# Peripherals.net
KiCad netlist of a schematic drawn in Altium Designer
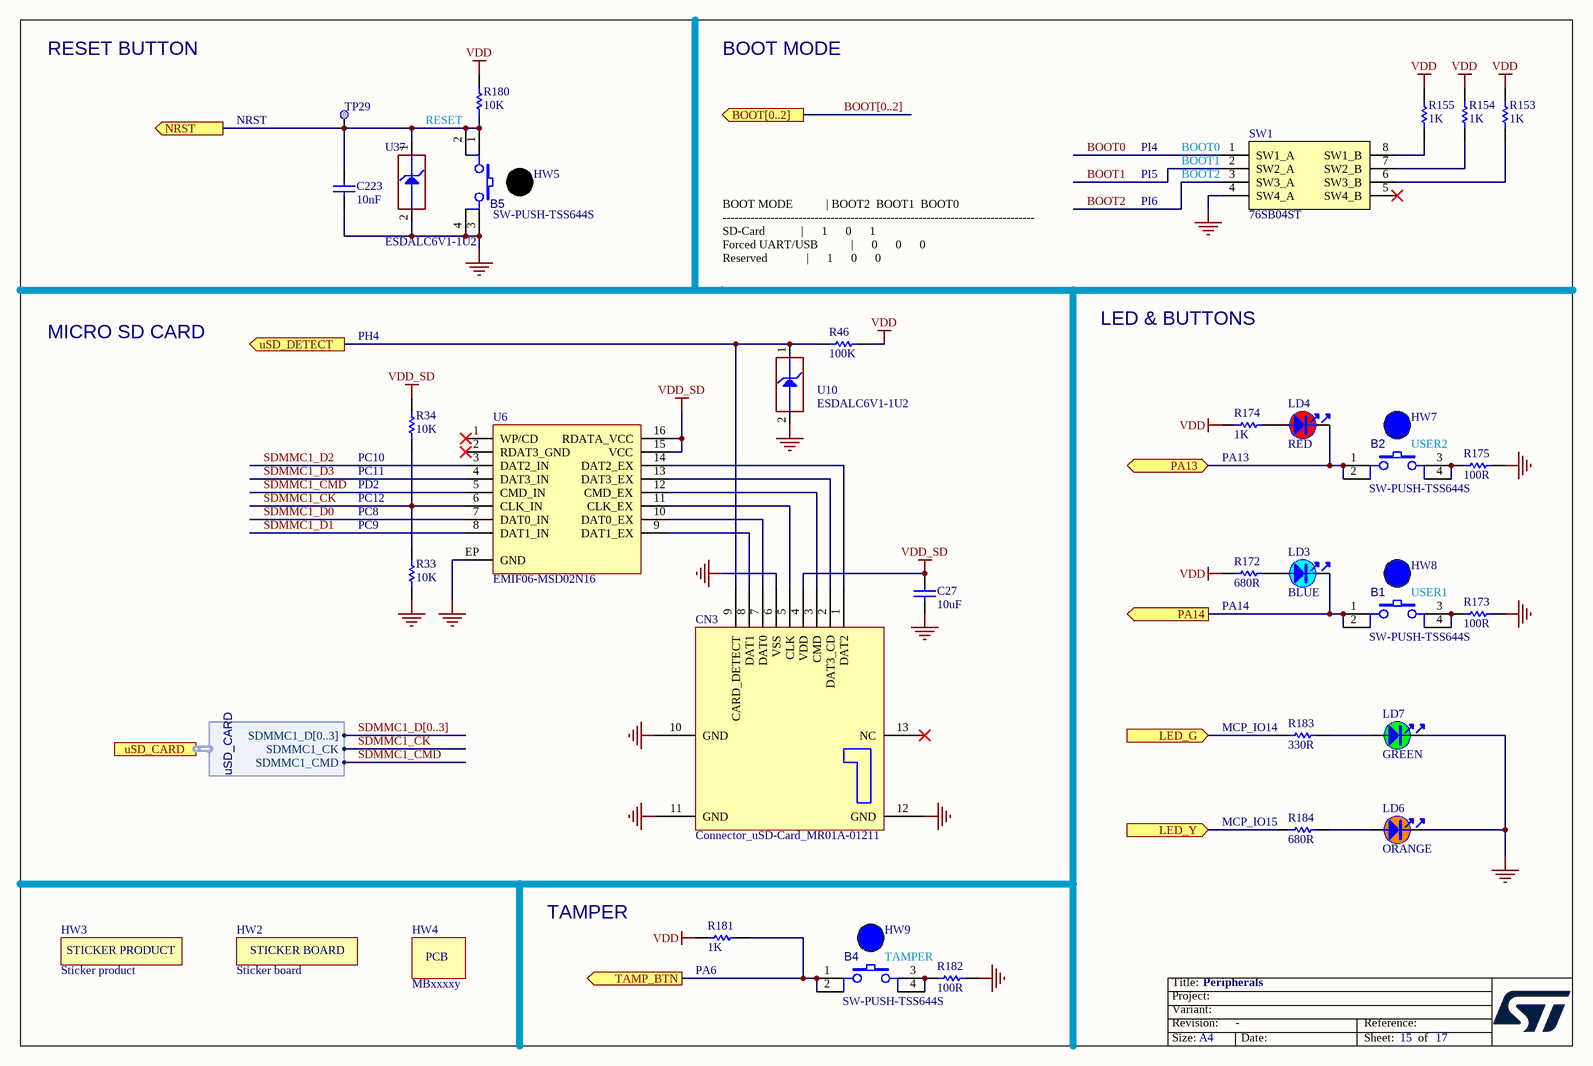
[diagram p0: Peripherals.SchDoc]

(export (version "E")
  (design (tool "Eeschema 10.0.6"))
  (components
    (comp (ref "B1")
      (value "SW-PUSH-TSS644S")
      (footprint "SWI_KNITTER_TSS644S")
      (description "Push Button, NO, 0.05A, 12V, 2.6N, SMD, 9.0x6.2mm, T=7.3mm, changeable caps KTSC-6xx")
      (fields
        (field (name "INTERNAL_PART_NUMBER") "MCD-02417")
        (field (name "MANUFACTURER_PART_NUMBER") "TSS644S")
      )
      (libsource (lib "MCD_PARTS_database") (part "SW_PUSH_SMD"))
    )
    (comp (ref "B2")
      (value "SW-PUSH-TSS644S")
      (footprint "SWI_KNITTER_TSS644S")
      (description "Push Button, NO, 0.05A, 12V, 2.6N, SMD, 9.0x6.2mm, T=7.3mm, changeable caps KTSC-6xx")
      (fields
        (field (name "INTERNAL_PART_NUMBER") "MCD-02417")
        (field (name "MANUFACTURER_PART_NUMBER") "TSS644S")
      )
      (libsource (lib "MCD_PARTS_database") (part "SW_PUSH_SMD"))
    )
    (comp (ref "B4")
      (value "SW-PUSH-TSS644S")
      (footprint "SWI_KNITTER_TSS644S")
      (description "Push Button, NO, 0.05A, 12V, 2.6N, SMD, 9.0x6.2mm, T=7.3mm, changeable caps KTSC-6xx")
      (fields
        (field (name "INTERNAL_PART_NUMBER") "MCD-02417")
        (field (name "MANUFACTURER_PART_NUMBER") "TSS644S")
      )
      (libsource (lib "MCD_PARTS_database") (part "SW_PUSH_SMD"))
    )
    (comp (ref "B5")
      (value "SW-PUSH-TSS644S")
      (footprint "SWI_KNITTER_TSS644S")
      (description "Push Button, NO, 0.05A, 12V, 2.6N, SMD, 9.0x6.2mm, T=7.3mm, changeable caps KTSC-6xx")
      (fields
        (field (name "INTERNAL_PART_NUMBER") "MCD-02417")
        (field (name "MANUFACTURER_PART_NUMBER") "TSS644S")
      )
      (libsource (lib "MCD_PARTS_database") (part "SW_PUSH_SMD"))
    )
    (comp (ref "C27")
      (value "10uF")
      (footprint "C0603")
      (description "Capacitor, MLCC, 10uF, 10V, X5R, +/-10%, 0603, T=0.8mm")
      (fields
        (field (name "INTERNAL_PART_NUMBER") "MCD-00099")
        (field (name "MANUFACTURER_PART_NUMBER") "GRM188R61A106KE69D")
      )
      (libsource (lib "MCD_PARTS_database") (part "Capacitor"))
    )
    (comp (ref "C223")
      (value "10nF")
      (footprint "C0402")
      (description "Capacitor, MLCC, 10nF, 50V, X7R, +/-10%, 0402, T=0.5mm")
      (fields
        (field (name "INTERNAL_PART_NUMBER") "MCD-02198")
        (field (name "MANUFACTURER_PART_NUMBER") "CC0402KRX7R9BB103")
      )
      (libsource (lib "MCD_PARTS_database") (part "Capacitor"))
    )
    (comp (ref "CN3")
      (value "Connector_uSD-Card_MR01A-01211")
      (footprint "CON_MICROSD_ATOM_MR01A-01211")
      (description "Connector_uSD Card, Top Mnt Push-Push")
      (fields
        (field (name "INTERNAL_PART_NUMBER") "MCD-00653")
        (field (name "MANUFACTURER_PART_NUMBER") "MR01A-01211")
      )
      (libsource (lib "MCD_PARTS_database") (part "MR01A-01211"))
    )
    (comp (ref "HW2")
      (value "Sticker board")
      (footprint "STICKER_BOARD_25X9")
      (description "Sticker Board 25x9 mm")
      (fields (field (name "INTERNAL_PART_NUMBER") "MCD-00235") (field (name "Comment") "STICKER_BOARD"))
      (libsource (lib "MCD_PARTS_database") (part "STICKER_BOARD"))
    )
    (comp (ref "HW3")
      (value "Sticker product")
      (footprint "STICKER_PRODUCT_25X9")
      (description "Sticker product 25x9 mm")
      (fields (field (name "INTERNAL_PART_NUMBER") "MCD-00547") (field (name "Comment") "STICKER_PRODUCT"))
      (libsource (lib "MCD_PARTS_database") (part "STICKER_PRODUCT"))
    )
    (comp (ref "HW4")
      (value "MBxxxxy")
      (description "PCB, xxxx for PCB number, Y for PCB revision")
      (fields
        (field (name "INTERNAL_PART_NUMBER") "MCD-00216")
        (field (name "MANUFACTURER_PART_NUMBER") "n/a")
      )
      (libsource (lib "MCD_PARTS_database") (part "PCB"))
    )
    (comp (ref "HW5")
      (value "SW-CAP-KTSC-62K")
      (description "Black round cap for TSS6x series")
      (fields
        (field (name "INTERNAL_PART_NUMBER") "MCD-02420")
        (field (name "MANUFACTURER") "KNITTER-SWITCH")
      )
      (libsource (lib "MCD_PARTS_database") (part "SW-CAP-Black"))
    )
    (comp (ref "HW7")
      (value "Blue Hat")
      (description "Switch hat, blue, For KTSC-62B")
      (fields (field (name "INTERNAL_PART_NUMBER") "MCD-02136") (field (name "MANUFACTURER") "APEM INC"))
      (libsource (lib "MCD_PARTS_database") (part "BUTTON_HAT_BLUE"))
    )
    (comp (ref "HW8")
      (value "Blue Hat")
      (description "Switch hat, blue, For KTSC-62B")
      (fields (field (name "INTERNAL_PART_NUMBER") "MCD-02136") (field (name "MANUFACTURER") "APEM INC"))
      (libsource (lib "MCD_PARTS_database") (part "BUTTON_HAT_BLUE"))
    )
    (comp (ref "HW9")
      (value "Blue Hat")
      (description "Switch hat, blue, For KTSC-62B")
      (fields (field (name "INTERNAL_PART_NUMBER") "MCD-02136") (field (name "MANUFACTURER") "APEM INC"))
      (libsource (lib "MCD_PARTS_database") (part "BUTTON_HAT_BLUE"))
    )
    (comp (ref "LD3")
      (value "BLUE")
      (footprint "LED_0603_SMD-B_BLUE_H0P4")
      (description "LED Blue, 0603 SMD, Forward Voltage Min=2,8V, Max=3,1V")
      (fields
        (field (name "INTERNAL_PART_NUMBER") "MCD-01131")
        (field (name "MANUFACTURER_PART_NUMBER") "19-217-BHC-ZL1M2RY-3T")
      )
      (libsource (lib "MCD_PARTS_database") (part "LED_blue"))
    )
    (comp (ref "LD4")
      (value "RED")
      (footprint "LED_0603_RED")
      (description "LED, Red, 0603")
      (fields
        (field (name "INTERNAL_PART_NUMBER") "MCD-00049")
        (field (name "MANUFACTURER_PART_NUMBER") "19-213-R6C-AP1Q2B/3T")
      )
      (libsource (lib "MCD_PARTS_database") (part "LED_red"))
    )
    (comp (ref "LD6")
      (value "ORANGE")
      (footprint "LED_0603_ORANGE_H0P4")
      (description "LED, Orange, 0603")
      (fields
        (field (name "INTERNAL_PART_NUMBER") "MCD-00321")
        (field (name "MANUFACTURER_PART_NUMBER") "19-217/S2C-AM2N2VY/3T")
      )
      (libsource (lib "MCD_PARTS_database") (part "LED_orange"))
    )
    (comp (ref "LD7")
      (value "GREEN")
      (footprint "LED_0603_GREEN")
      (description "LED, Green, 0603")
      (fields
        (field (name "INTERNAL_PART_NUMBER") "MCD-00050")
        (field (name "MANUFACTURER_PART_NUMBER") "19-213SYGC/S530-E2/TR8")
      )
      (libsource (lib "MCD_PARTS_database") (part "LED_green"))
    )
    (comp (ref "R33")
      (value "10K")
      (footprint "R0402")
      (description "Resistor, 10K, 0402, +/-1%, 1/16W")
      (fields
        (field (name "INTERNAL_PART_NUMBER") "MCD-00053")
        (field (name "MANUFACTURER_PART_NUMBER") "RC0402FR-0710KL")
      )
      (libsource (lib "MCD_PARTS_database") (part "Resistor"))
    )
    (comp (ref "R34")
      (value "10K")
      (footprint "R0402")
      (description "Resistor, 10K, 0402, +/-1%, 1/16W")
      (fields
        (field (name "INTERNAL_PART_NUMBER") "MCD-00053")
        (field (name "MANUFACTURER_PART_NUMBER") "RC0402FR-0710KL")
      )
      (libsource (lib "MCD_PARTS_database") (part "Resistor"))
    )
    (comp (ref "R46")
      (value "100K")
      (footprint "R0402")
      (description "Resistor, 100K, 0402, +/-1%, 1/16W")
      (fields (field (name "INTERNAL_PART_NUMBER") "MCD-00059") (field (name "MANUFACTURER") "YAGEO"))
      (libsource (lib "MCD_PARTS_database") (part "Resistor"))
    )
    (comp (ref "R153")
      (value "1K")
      (footprint "R0402")
      (description "Resistor, 1K, 0402, +/-1%,1/16W")
      (fields
        (field (name "INTERNAL_PART_NUMBER") "MCD-00061")
        (field (name "MANUFACTURER_PART_NUMBER") "RC0402FR-071KL")
      )
      (libsource (lib "MCD_PARTS_database") (part "Resistor"))
    )
    (comp (ref "R154")
      (value "1K")
      (footprint "R0402")
      (description "Resistor, 1K, 0402, +/-1%,1/16W")
      (fields
        (field (name "INTERNAL_PART_NUMBER") "MCD-00061")
        (field (name "MANUFACTURER_PART_NUMBER") "RC0402FR-071KL")
      )
      (libsource (lib "MCD_PARTS_database") (part "Resistor"))
    )
    (comp (ref "R155")
      (value "1K")
      (footprint "R0402")
      (description "Resistor, 1K, 0402, +/-1%,1/16W")
      (fields
        (field (name "INTERNAL_PART_NUMBER") "MCD-00061")
        (field (name "MANUFACTURER_PART_NUMBER") "RC0402FR-071KL")
      )
      (libsource (lib "MCD_PARTS_database") (part "Resistor"))
    )
    (comp (ref "R172")
      (value "680R")
      (footprint "R0402")
      (description "Resistor, 680R, 0402, +/-1%, 1/16W")
      (fields
        (field (name "INTERNAL_PART_NUMBER") "MCD-00507")
        (field (name "MANUFACTURER_PART_NUMBER") "RC0402FR-07680RL")
      )
      (libsource (lib "MCD_PARTS_database") (part "Resistor"))
    )
    (comp (ref "R173")
      (value "100R")
      (footprint "R0402")
      (description "Resistor, 100R, 0402, +/- 1%, 1/16W")
      (fields
        (field (name "INTERNAL_PART_NUMBER") "MCD-00067")
        (field (name "MANUFACTURER_PART_NUMBER") "RC0402FR-07100RL")
      )
      (libsource (lib "MCD_PARTS_database") (part "Resistor"))
    )
    (comp (ref "R174")
      (value "1K")
      (footprint "R0402")
      (description "Resistor, 1K, 0402, +/-1%,1/16W")
      (fields
        (field (name "INTERNAL_PART_NUMBER") "MCD-00061")
        (field (name "MANUFACTURER_PART_NUMBER") "RC0402FR-071KL")
      )
      (libsource (lib "MCD_PARTS_database") (part "Resistor"))
    )
    (comp (ref "R175")
      (value "100R")
      (footprint "R0402")
      (description "Resistor, 100R, 0402, +/- 1%, 1/16W")
      (fields
        (field (name "INTERNAL_PART_NUMBER") "MCD-00067")
        (field (name "MANUFACTURER_PART_NUMBER") "RC0402FR-07100RL")
      )
      (libsource (lib "MCD_PARTS_database") (part "Resistor"))
    )
    (comp (ref "R180")
      (value "10K")
      (footprint "R0402")
      (description "Resistor, 10K, 0402, +/-1%, 1/16W")
      (fields
        (field (name "INTERNAL_PART_NUMBER") "MCD-00053")
        (field (name "MANUFACTURER_PART_NUMBER") "RC0402FR-0710KL")
      )
      (libsource (lib "MCD_PARTS_database") (part "Resistor"))
    )
    (comp (ref "R181")
      (value "1K")
      (footprint "R0402")
      (description "Resistor, 1K, 0402, +/-1%,1/16W")
      (fields
        (field (name "INTERNAL_PART_NUMBER") "MCD-00061")
        (field (name "MANUFACTURER_PART_NUMBER") "RC0402FR-071KL")
      )
      (libsource (lib "MCD_PARTS_database") (part "Resistor"))
    )
    (comp (ref "R182")
      (value "100R")
      (footprint "R0402")
      (description "Resistor, 100R, 0402, +/- 1%, 1/16W")
      (fields
        (field (name "INTERNAL_PART_NUMBER") "MCD-00067")
        (field (name "MANUFACTURER_PART_NUMBER") "RC0402FR-07100RL")
      )
      (libsource (lib "MCD_PARTS_database") (part "Resistor"))
    )
    (comp (ref "R183")
      (value "330R")
      (footprint "R0402")
      (description "Resistor, 330R, 0402, +/-1%, 1/16W")
      (fields
        (field (name "INTERNAL_PART_NUMBER") "MCD-00062")
        (field (name "MANUFACTURER_PART_NUMBER") "RC0402FR-07330RL")
      )
      (libsource (lib "MCD_PARTS_database") (part "Resistor"))
    )
    (comp (ref "R184")
      (value "680R")
      (footprint "R0402")
      (description "Resistor, 680R, 0402, +/-1%, 1/16W")
      (fields
        (field (name "INTERNAL_PART_NUMBER") "MCD-00507")
        (field (name "MANUFACTURER_PART_NUMBER") "RC0402FR-07680RL")
      )
      (libsource (lib "MCD_PARTS_database") (part "Resistor"))
    )
    (comp (ref "SW1")
      (value "76SB04ST")
      (footprint "SWI_GRAYHILL-INC_76SB04ST")
      (description "Quad SPST switch, TH, 2.54mm pitch, height 7.5mm")
      (fields (field (name "INTERNAL_PART_NUMBER") "MCD-02256") (field (name "MANUFACTURER") "GRAYHILL"))
      (libsource (lib "MCD_PARTS_database") (part "76SB04ST"))
    )
    (comp (ref "TP29")
      (value "Test Point")
      (footprint "TP_SMD_1MM")
      (description "Test Point 1mm")
      (fields (field (name "INTERNAL_PART_NUMBER") "MCD-00074"))
      (libsource (lib "MCD_PARTS_database") (part "Test Point"))
    )
    (comp (ref "U6")
      (value "EMIF06-MSD02N16")
      (footprint "ESD_UQFN16L-EPAD_3P5X1P2_P040")
      (description "ESD protection for SD card 2.0")
      (fields (field (name "INTERNAL_PART_NUMBER") "MCD-00249") (field (name "BMS_PART_NUMBER") "9179003"))
      (libsource (lib "MCD_PARTS_database") (part "EMIF06-MSD02N16"))
    )
    (comp (ref "U10")
      (value "ESDALC6V1-1U2")
      (footprint "ESD_ST0201")
      (description "ESD protection 6V1")
      (fields
        (field (name "INTERNAL_PART_NUMBER") "MCD-00170")
        (field (name "MANUFACTURER") "STMICROELECTRONICS")
      )
      (libsource (lib "MCD_PARTS_database") (part "ESD-TRANSIL"))
    )
    (comp (ref "U37")
      (value "ESDALC6V1-1U2")
      (footprint "ESD_ST0201")
      (description "ESD protection 6V1")
      (fields
        (field (name "INTERNAL_PART_NUMBER") "MCD-00170")
        (field (name "MANUFACTURER") "STMICROELECTRONICS")
      )
      (libsource (lib "MCD_PARTS_database") (part "ESD-TRANSIL"))
    )
  )
  (nets
    (net (code "2") (name "/BOOT0") (class "Default")
      (node (ref "SW1") (pin "1") (pinfunction "SW1_A_1") (pintype "passive"))
    )
    (net (code "3") (name "/BOOT1") (class "Default")
      (node (ref "SW1") (pin "2") (pinfunction "SW2_A_2") (pintype "passive"))
    )
    (net (code "4") (name "/BOOT2") (class "Default")
      (node (ref "SW1") (pin "3") (pinfunction "SW3_A_3") (pintype "passive"))
    )
    (net (code "6") (name "/LED_G") (class "Default")
      (node (ref "R183") (pin "1") (pinfunction "1_1") (pintype "passive"))
    )
    (net (code "7") (name "/LED_Y") (class "Default")
      (node (ref "R184") (pin "1") (pinfunction "1_1") (pintype "passive"))
    )
    (net (code "8") (name "/NRST") (class "Default")
      (node (ref "B5") (pin "1") (pinfunction "1_1") (pintype "passive"))
      (node (ref "B5") (pin "2") (pinfunction "2_2") (pintype "passive"))
      (node (ref "C223") (pin "2") (pinfunction "2_2") (pintype "passive"))
      (node (ref "R180") (pin "1") (pinfunction "1_1") (pintype "passive"))
      (node (ref "TP29") (pin "1") (pinfunction "1_1") (pintype "passive"))
      (node (ref "U37") (pin "1") (pinfunction "IO1_1") (pintype "passive"))
    )
    (net (code "9") (name "/PA13") (class "Default")
      (node (ref "B2") (pin "1") (pinfunction "1_1") (pintype "passive"))
      (node (ref "B2") (pin "2") (pinfunction "2_2") (pintype "passive"))
      (node (ref "LD4") (pin "2") (pintype "passive"))
    )
    (net (code "10") (name "/PA14") (class "Default")
      (node (ref "B1") (pin "1") (pinfunction "1_1") (pintype "passive"))
      (node (ref "B1") (pin "2") (pinfunction "2_2") (pintype "passive"))
      (node (ref "LD3") (pin "2") (pintype "passive"))
    )
    (net (code "11") (name "/SDMMC1_CK") (class "Default")
      (node (ref "R33") (pin "2") (pinfunction "2_2") (pintype "passive"))
      (node (ref "R34") (pin "1") (pinfunction "1_1") (pintype "passive"))
      (node (ref "U6") (pin "6") (pinfunction "CLK_IN_6") (pintype "passive"))
    )
    (net (code "12") (name "/SDMMC1_CMD") (class "Default")
      (node (ref "U6") (pin "5") (pinfunction "CMD_IN_5") (pintype "passive"))
    )
    (net (code "13") (name "/SDMMC1_D0") (class "Default")
      (node (ref "U6") (pin "7") (pinfunction "DAT0_IN_7") (pintype "passive"))
    )
    (net (code "14") (name "/SDMMC1_D1") (class "Default")
      (node (ref "U6") (pin "8") (pinfunction "DAT1_IN_8") (pintype "passive"))
    )
    (net (code "15") (name "/SDMMC1_D2") (class "Default")
      (node (ref "U6") (pin "3") (pinfunction "DAT2_IN_3") (pintype "passive"))
    )
    (net (code "16") (name "/SDMMC1_D3") (class "Default")
      (node (ref "U6") (pin "4") (pinfunction "DAT3_IN_4") (pintype "passive"))
    )
    (net (code "17") (name "/TAMP_BTN") (class "Default")
      (node (ref "B4") (pin "1") (pinfunction "1_1") (pintype "passive"))
      (node (ref "B4") (pin "2") (pinfunction "2_2") (pintype "passive"))
      (node (ref "R181") (pin "1") (pinfunction "1_1") (pintype "passive"))
    )
    (net (code "19") (name "/uSD_DETECT") (class "Default")
      (node (ref "CN3") (pin "9") (pinfunction "CARD_DETECT_9") (pintype "passive"))
      (node (ref "R46") (pin "2") (pinfunction "2_2") (pintype "passive"))
      (node (ref "U10") (pin "1") (pinfunction "IO1_1") (pintype "passive"))
    )
    (net (code "21") (name "GND") (class "Default")
      (node (ref "B5") (pin "3") (pinfunction "3_3") (pintype "passive"))
      (node (ref "B5") (pin "4") (pinfunction "4_4") (pintype "passive"))
      (node (ref "C223") (pin "1") (pinfunction "1_1") (pintype "passive"))
      (node (ref "C27") (pin "1") (pinfunction "1_1") (pintype "passive"))
      (node (ref "CN3") (pin "10") (pinfunction "GND_10") (pintype "passive"))
      (node (ref "CN3") (pin "11") (pinfunction "GND_11") (pintype "passive"))
      (node (ref "CN3") (pin "12") (pinfunction "GND_12") (pintype "passive"))
      (node (ref "CN3") (pin "6") (pinfunction "VSS_6") (pintype "passive"))
      (node (ref "LD6") (pin "2") (pintype "passive"))
      (node (ref "LD7") (pin "2") (pintype "passive"))
      (node (ref "R173") (pin "2") (pinfunction "2_2") (pintype "passive"))
      (node (ref "R175") (pin "2") (pinfunction "2_2") (pintype "passive"))
      (node (ref "R182") (pin "2") (pinfunction "2_2") (pintype "passive"))
      (node (ref "R33") (pin "1") (pinfunction "1_1") (pintype "passive"))
      (node (ref "SW1") (pin "4") (pinfunction "SW4_A_4") (pintype "passive"))
      (node (ref "U10") (pin "2") (pinfunction "GND_2") (pintype "passive"))
      (node (ref "U37") (pin "2") (pinfunction "GND_2") (pintype "passive"))
      (node (ref "U6") (pin "EP") (pinfunction "GND_EP") (pintype "passive"))
    )
    (net (code "22") (name "Net-(B1-Pad3)") (class "Default")
      (node (ref "B1") (pin "3") (pinfunction "3_3") (pintype "passive"))
      (node (ref "B1") (pin "4") (pinfunction "4_4") (pintype "passive"))
      (node (ref "R173") (pin "1") (pinfunction "1_1") (pintype "passive"))
    )
    (net (code "23") (name "Net-(B2-Pad3)") (class "Default")
      (node (ref "B2") (pin "3") (pinfunction "3_3") (pintype "passive"))
      (node (ref "B2") (pin "4") (pinfunction "4_4") (pintype "passive"))
      (node (ref "R175") (pin "1") (pinfunction "1_1") (pintype "passive"))
    )
    (net (code "24") (name "Net-(B4-Pad3)") (class "Default")
      (node (ref "B4") (pin "3") (pinfunction "3_3") (pintype "passive"))
      (node (ref "B4") (pin "4") (pinfunction "4_4") (pintype "passive"))
      (node (ref "R182") (pin "1") (pinfunction "1_1") (pintype "passive"))
    )
    (net (code "25") (name "Net-(CN3-CLK)") (class "Default")
      (node (ref "CN3") (pin "5") (pinfunction "CLK_5") (pintype "passive"))
      (node (ref "U6") (pin "11") (pinfunction "CLK_EX_11") (pintype "passive"))
    )
    (net (code "26") (name "Net-(CN3-CMD)") (class "Default")
      (node (ref "CN3") (pin "3") (pinfunction "CMD_3") (pintype "passive"))
      (node (ref "U6") (pin "12") (pinfunction "CMD_EX_12") (pintype "passive"))
    )
    (net (code "27") (name "Net-(CN3-DAT0)") (class "Default")
      (node (ref "CN3") (pin "7") (pinfunction "DAT0_7") (pintype "passive"))
      (node (ref "U6") (pin "10") (pinfunction "DAT0_EX_10") (pintype "passive"))
    )
    (net (code "28") (name "Net-(CN3-DAT1)") (class "Default")
      (node (ref "CN3") (pin "8") (pinfunction "DAT1_8") (pintype "passive"))
      (node (ref "U6") (pin "9") (pinfunction "DAT1_EX_9") (pintype "passive"))
    )
    (net (code "29") (name "Net-(CN3-DAT2)") (class "Default")
      (node (ref "CN3") (pin "1") (pinfunction "DAT2_1") (pintype "passive"))
      (node (ref "U6") (pin "14") (pinfunction "DAT2_EX_14") (pintype "passive"))
    )
    (net (code "30") (name "Net-(CN3-DAT3_CD)") (class "Default")
      (node (ref "CN3") (pin "2") (pinfunction "DAT3_CD_2") (pintype "passive"))
      (node (ref "U6") (pin "13") (pinfunction "DAT3_EX_13") (pintype "passive"))
    )
    (net (code "31") (name "Net-(LD3-Pad1)") (class "Default")
      (node (ref "LD3") (pin "1") (pintype "passive"))
      (node (ref "R172") (pin "1") (pinfunction "1_1") (pintype "passive"))
    )
    (net (code "32") (name "Net-(LD4-Pad1)") (class "Default")
      (node (ref "LD4") (pin "1") (pintype "passive"))
      (node (ref "R174") (pin "1") (pinfunction "1_1") (pintype "passive"))
    )
    (net (code "33") (name "Net-(LD6-Pad1)") (class "Default")
      (node (ref "LD6") (pin "1") (pintype "passive"))
      (node (ref "R184") (pin "2") (pinfunction "2_2") (pintype "passive"))
    )
    (net (code "34") (name "Net-(LD7-Pad1)") (class "Default")
      (node (ref "LD7") (pin "1") (pintype "passive"))
      (node (ref "R183") (pin "2") (pinfunction "2_2") (pintype "passive"))
    )
    (net (code "35") (name "Net-(SW1-SW1_B)") (class "Default")
      (node (ref "R155") (pin "1") (pinfunction "1_1") (pintype "passive"))
      (node (ref "SW1") (pin "8") (pinfunction "SW1_B_8") (pintype "passive"))
    )
    (net (code "36") (name "Net-(SW1-SW2_B)") (class "Default")
      (node (ref "R154") (pin "1") (pinfunction "1_1") (pintype "passive"))
      (node (ref "SW1") (pin "7") (pinfunction "SW2_B_7") (pintype "passive"))
    )
    (net (code "37") (name "Net-(SW1-SW3_B)") (class "Default")
      (node (ref "R153") (pin "1") (pinfunction "1_1") (pintype "passive"))
      (node (ref "SW1") (pin "6") (pinfunction "SW3_B_6") (pintype "passive"))
    )
    (net (code "38") (name "VDD") (class "Default")
      (node (ref "R153") (pin "2") (pinfunction "2_2") (pintype "passive"))
      (node (ref "R154") (pin "2") (pinfunction "2_2") (pintype "passive"))
      (node (ref "R155") (pin "2") (pinfunction "2_2") (pintype "passive"))
      (node (ref "R172") (pin "2") (pinfunction "2_2") (pintype "passive"))
      (node (ref "R174") (pin "2") (pinfunction "2_2") (pintype "passive"))
      (node (ref "R180") (pin "2") (pinfunction "2_2") (pintype "passive"))
      (node (ref "R181") (pin "2") (pinfunction "2_2") (pintype "passive"))
      (node (ref "R46") (pin "1") (pinfunction "1_1") (pintype "passive"))
    )
    (net (code "39") (name "VDD_SD") (class "Default")
      (node (ref "C27") (pin "2") (pinfunction "2_2") (pintype "passive"))
      (node (ref "CN3") (pin "4") (pinfunction "VDD_4") (pintype "passive"))
      (node (ref "R34") (pin "2") (pinfunction "2_2") (pintype "passive"))
      (node (ref "U6") (pin "15") (pinfunction "VCC_15") (pintype "passive"))
      (node (ref "U6") (pin "16") (pinfunction "RDATA_VCC_16") (pintype "passive"))
    )
    (net (code "40") (name "unconnected-(CN3-NC-Pad13)") (class "Default")
      (node (ref "CN3") (pin "13") (pinfunction "NC_13") (pintype "passive+no_connect"))
    )
    (net (code "41") (name "unconnected-(SW1-SW4_B-Pad5)") (class "Default")
      (node (ref "SW1") (pin "5") (pinfunction "SW4_B_5") (pintype "passive+no_connect"))
    )
    (net (code "42") (name "unconnected-(U6-RDAT3_GND-Pad2)") (class "Default")
      (node (ref "U6") (pin "2") (pinfunction "RDAT3_GND_2") (pintype "passive+no_connect"))
    )
    (net (code "43") (name "unconnected-(U6-WP{slash}CD-Pad1)") (class "Default")
      (node (ref "U6") (pin "1") (pinfunction "WP/CD_1") (pintype "passive+no_connect"))
    )
  )
)
